# cpuboard_pic32mx_rev01.net
KiCad netlist of a schematic drawn in EAGLE
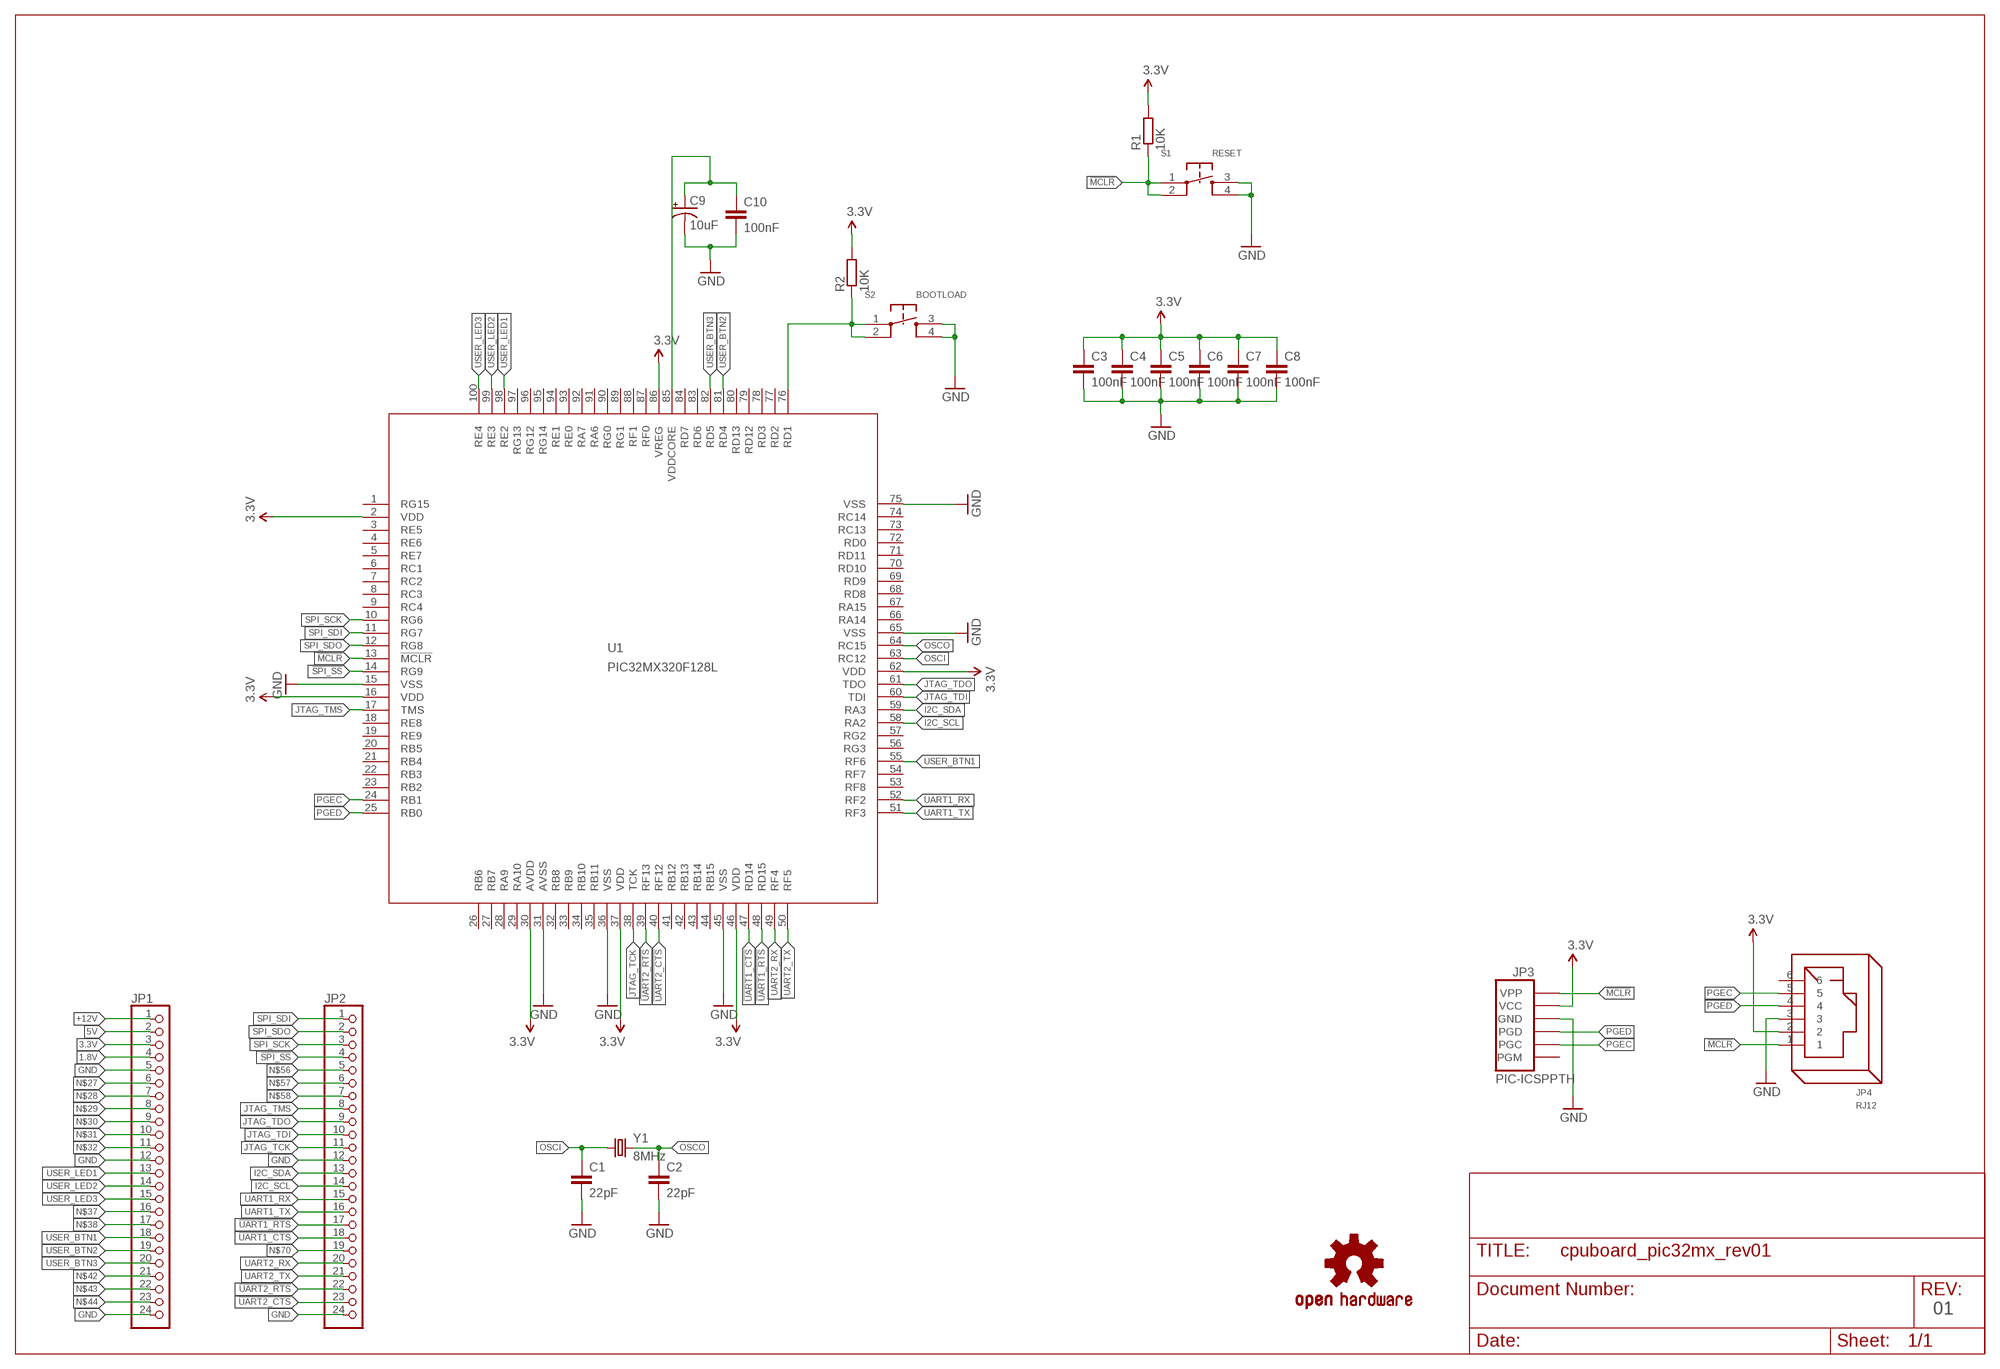
[diagram p0: schematic, sheet 1]

(export (version "E")
  (design (tool "Eeschema 10.0.6"))
  (components
    (comp (ref "C1")
      (value "22pF")
      (footprint "eagle-import:C0805K")
      (libsource (lib "eagle-import") (part "C-EUC0805K"))
    )
    (comp (ref "C2")
      (value "22pF")
      (footprint "eagle-import:C0805K")
      (libsource (lib "eagle-import") (part "C-EUC0805K"))
    )
    (comp (ref "C3")
      (value "100nF")
      (footprint "eagle-import:C0805K")
      (libsource (lib "eagle-import") (part "C-EUC0805K"))
    )
    (comp (ref "C4")
      (value "100nF")
      (footprint "eagle-import:C0805K")
      (libsource (lib "eagle-import") (part "C-EUC0805K"))
    )
    (comp (ref "C5")
      (value "100nF")
      (footprint "eagle-import:C0805K")
      (libsource (lib "eagle-import") (part "C-EUC0805K"))
    )
    (comp (ref "C6")
      (value "100nF")
      (footprint "eagle-import:C0805K")
      (libsource (lib "eagle-import") (part "C-EUC0805K"))
    )
    (comp (ref "C7")
      (value "100nF")
      (footprint "eagle-import:C0805K")
      (libsource (lib "eagle-import") (part "C-EUC0805K"))
    )
    (comp (ref "C8")
      (value "100nF")
      (footprint "eagle-import:C0805K")
      (libsource (lib "eagle-import") (part "C-EUC0805K"))
    )
    (comp (ref "C9")
      (value "10uF")
      (footprint "eagle-import:PANASONIC_D")
      (libsource (lib "eagle-import") (part "CAP_POLD"))
    )
    (comp (ref "C10")
      (value "100nF")
      (footprint "eagle-import:C0805K")
      (libsource (lib "eagle-import") (part "C-EUC0805K"))
    )
    (comp (ref "JP1")
      (value "PINHD-1X24")
      (footprint "eagle-import:1X24")
      (libsource (lib "eagle-import") (part "PINHD-1X24"))
    )
    (comp (ref "JP2")
      (value "PINHD-1X24")
      (footprint "eagle-import:1X24")
      (libsource (lib "eagle-import") (part "PINHD-1X24"))
    )
    (comp (ref "JP3")
      (value "PIC-ICSPPTH")
      (footprint "eagle-import:MOLEX-1X6")
      (libsource (lib "eagle-import") (part "PIC-ICSPPTH"))
    )
    (comp (ref "JP4")
      (value "RJ12")
      (footprint "eagle-import:RJ12")
      (libsource (lib "eagle-import") (part "RJ12"))
    )
    (comp (ref "R1")
      (value "10K")
      (footprint "eagle-import:R0805")
      (libsource (lib "eagle-import") (part "R-EU_R0805"))
    )
    (comp (ref "R2")
      (value "10K")
      (footprint "eagle-import:R0805")
      (libsource (lib "eagle-import") (part "R-EU_R0805"))
    )
    (comp (ref "S1")
      (value "RESET")
      (footprint "eagle-import:SWITCH_TROUGHHOLE")
      (libsource (lib "eagle-import") (part "SWITCH_TH"))
    )
    (comp (ref "S2")
      (value "BOOTLOAD")
      (footprint "eagle-import:SWITCH_TROUGHHOLE")
      (libsource (lib "eagle-import") (part "SWITCH_TH"))
    )
    (comp (ref "U$1")
      (value "OSHW-LOGOS")
      (footprint "eagle-import:OSHW-LOGO-S")
      (libsource (lib "eagle-import") (part "OSHW-LOGOS"))
    )
    (comp (ref "U1")
      (value "PIC32MX320F128L")
      (footprint "eagle-import:SQFP-S-12X12-100")
      (fields (field (name "MPN") "PIC32MX320F128L-80I/PT"))
      (libsource (lib "eagle-import") (part "PIC32MX320F128L"))
    )
    (comp (ref "Y1")
      (value "8MHz")
      (footprint "eagle-import:HC49UP")
      (libsource (lib "eagle-import") (part "CRYSTALSMD"))
    )
  )
  (nets
    (net (code "1") (name "+12V") (class "Default")
      (node (ref "JP1") (pin "1") (pinfunction "1_1") (pintype "passive"))
    )
    (net (code "2") (name "/~{MCLR}") (class "Default")
      (node (ref "JP3") (pin "6") (pinfunction "VPP_6") (pintype "bidirectional"))
      (node (ref "JP4") (pin "1") (pinfunction "1_1") (pintype "bidirectional"))
      (node (ref "R1") (pin "1") (pinfunction "1_1") (pintype "passive"))
      (node (ref "S1") (pin "1") (pintype "bidirectional"))
      (node (ref "S1") (pin "2") (pintype "bidirectional"))
      (node (ref "U1") (pin "13") (pinfunction "~{MCLR}_13") (pintype "input"))
    )
    (net (code "3") (name "/~{SPI_SS}") (class "Default")
      (node (ref "JP2") (pin "4") (pinfunction "4_4") (pintype "passive"))
      (node (ref "U1") (pin "14") (pinfunction "RG9_14") (pintype "bidirectional"))
    )
    (net (code "4") (name "/~{UART1_CTS}") (class "Default")
      (node (ref "JP2") (pin "18") (pinfunction "18_18") (pintype "passive"))
      (node (ref "U1") (pin "47") (pinfunction "RD14_47") (pintype "bidirectional"))
    )
    (net (code "5") (name "/~{UART1_RTS}") (class "Default")
      (node (ref "JP2") (pin "17") (pinfunction "17_17") (pintype "passive"))
      (node (ref "U1") (pin "48") (pinfunction "RD15_48") (pintype "bidirectional"))
    )
    (net (code "6") (name "/~{UART2_CTS}") (class "Default")
      (node (ref "JP2") (pin "23") (pinfunction "23_23") (pintype "passive"))
      (node (ref "U1") (pin "40") (pinfunction "RF12_40") (pintype "bidirectional"))
    )
    (net (code "7") (name "/~{UART2_RTS}") (class "Default")
      (node (ref "JP2") (pin "22") (pinfunction "22_22") (pintype "passive"))
      (node (ref "U1") (pin "39") (pinfunction "RF13_39") (pintype "bidirectional"))
    )
    (net (code "8") (name "1.8V") (class "Default")
      (node (ref "JP1") (pin "4") (pinfunction "4_4") (pintype "passive"))
    )
    (net (code "9") (name "3.3V") (class "Default")
      (node (ref "C3") (pin "1") (pinfunction "1_1") (pintype "passive"))
      (node (ref "C4") (pin "1") (pinfunction "1_1") (pintype "passive"))
      (node (ref "C5") (pin "1") (pinfunction "1_1") (pintype "passive"))
      (node (ref "C6") (pin "1") (pinfunction "1_1") (pintype "passive"))
      (node (ref "C7") (pin "1") (pinfunction "1_1") (pintype "passive"))
      (node (ref "C8") (pin "1") (pinfunction "1_1") (pintype "passive"))
      (node (ref "JP1") (pin "3") (pinfunction "3_3") (pintype "passive"))
      (node (ref "JP3") (pin "5") (pinfunction "VCC_5") (pintype "bidirectional"))
      (node (ref "JP4") (pin "2") (pinfunction "2_2") (pintype "bidirectional"))
      (node (ref "R1") (pin "2") (pinfunction "2_2") (pintype "passive"))
      (node (ref "R2") (pin "2") (pinfunction "2_2") (pintype "passive"))
      (node (ref "U1") (pin "16") (pinfunction "VDD_16") (pintype "power_in"))
      (node (ref "U1") (pin "2") (pinfunction "VDD_2") (pintype "power_in"))
      (node (ref "U1") (pin "30") (pinfunction "AVDD_30") (pintype "power_in"))
      (node (ref "U1") (pin "37") (pinfunction "VDD_37") (pintype "power_in"))
      (node (ref "U1") (pin "46") (pinfunction "VDD_46") (pintype "power_in"))
      (node (ref "U1") (pin "62") (pinfunction "VDD_62") (pintype "power_in"))
      (node (ref "U1") (pin "86") (pinfunction "VREG_86") (pintype "passive"))
    )
    (net (code "10") (name "5V") (class "Default")
      (node (ref "JP1") (pin "2") (pinfunction "2_2") (pintype "passive"))
    )
    (net (code "11") (name "GND") (class "Default")
      (node (ref "C1") (pin "2") (pinfunction "2_2") (pintype "passive"))
      (node (ref "C10") (pin "2") (pinfunction "2_2") (pintype "passive"))
      (node (ref "C2") (pin "2") (pinfunction "2_2") (pintype "passive"))
      (node (ref "C3") (pin "2") (pinfunction "2_2") (pintype "passive"))
      (node (ref "C4") (pin "2") (pinfunction "2_2") (pintype "passive"))
      (node (ref "C5") (pin "2") (pinfunction "2_2") (pintype "passive"))
      (node (ref "C6") (pin "2") (pinfunction "2_2") (pintype "passive"))
      (node (ref "C7") (pin "2") (pinfunction "2_2") (pintype "passive"))
      (node (ref "C8") (pin "2") (pinfunction "2_2") (pintype "passive"))
      (node (ref "C9") (pin "-") (pinfunction "-_-") (pintype "passive"))
      (node (ref "JP1") (pin "12") (pinfunction "12_12") (pintype "passive"))
      (node (ref "JP1") (pin "24") (pinfunction "24_24") (pintype "passive"))
      (node (ref "JP1") (pin "5") (pinfunction "5_5") (pintype "passive"))
      (node (ref "JP2") (pin "12") (pinfunction "12_12") (pintype "passive"))
      (node (ref "JP2") (pin "24") (pinfunction "24_24") (pintype "passive"))
      (node (ref "JP3") (pin "4") (pinfunction "GND_4") (pintype "bidirectional"))
      (node (ref "JP4") (pin "3") (pinfunction "3_3") (pintype "bidirectional"))
      (node (ref "S1") (pin "3") (pintype "bidirectional"))
      (node (ref "S1") (pin "4") (pintype "bidirectional"))
      (node (ref "S2") (pin "3") (pintype "bidirectional"))
      (node (ref "S2") (pin "4") (pintype "bidirectional"))
      (node (ref "U1") (pin "15") (pinfunction "VSS_15") (pintype "power_in"))
      (node (ref "U1") (pin "31") (pinfunction "AVSS_31") (pintype "power_in"))
      (node (ref "U1") (pin "36") (pinfunction "VSS_36") (pintype "power_in"))
      (node (ref "U1") (pin "45") (pinfunction "VSS_45") (pintype "power_in"))
      (node (ref "U1") (pin "65") (pinfunction "VSS_65") (pintype "power_in"))
      (node (ref "U1") (pin "75") (pinfunction "VSS_75") (pintype "power_in"))
    )
    (net (code "12") (name "I2C_SCL") (class "Default")
      (node (ref "JP2") (pin "14") (pinfunction "14_14") (pintype "passive"))
      (node (ref "U1") (pin "58") (pinfunction "RA2_58") (pintype "bidirectional"))
    )
    (net (code "13") (name "I2C_SDA") (class "Default")
      (node (ref "JP2") (pin "13") (pinfunction "13_13") (pintype "passive"))
      (node (ref "U1") (pin "59") (pinfunction "RA3_59") (pintype "bidirectional"))
    )
    (net (code "14") (name "JTAG_TCK") (class "Default")
      (node (ref "JP2") (pin "11") (pinfunction "11_11") (pintype "passive"))
      (node (ref "U1") (pin "38") (pinfunction "TCK_38") (pintype "input"))
    )
    (net (code "15") (name "JTAG_TDI") (class "Default")
      (node (ref "JP2") (pin "10") (pinfunction "10_10") (pintype "passive"))
      (node (ref "U1") (pin "60") (pinfunction "TDI_60") (pintype "input"))
    )
    (net (code "16") (name "JTAG_TDO") (class "Default")
      (node (ref "JP2") (pin "9") (pinfunction "9_9") (pintype "passive"))
      (node (ref "U1") (pin "61") (pinfunction "TDO_61") (pintype "output"))
    )
    (net (code "17") (name "JTAG_TMS") (class "Default")
      (node (ref "JP2") (pin "8") (pinfunction "8_8") (pintype "passive"))
      (node (ref "U1") (pin "17") (pinfunction "TMS_17") (pintype "input"))
    )
    (net (code "18") (name "N$27") (class "Default")
      (node (ref "JP1") (pin "6") (pinfunction "6_6") (pintype "passive"))
    )
    (net (code "19") (name "N$28") (class "Default")
      (node (ref "JP1") (pin "7") (pinfunction "7_7") (pintype "passive"))
    )
    (net (code "20") (name "N$29") (class "Default")
      (node (ref "JP1") (pin "8") (pinfunction "8_8") (pintype "passive"))
    )
    (net (code "21") (name "N$30") (class "Default")
      (node (ref "JP1") (pin "9") (pinfunction "9_9") (pintype "passive"))
    )
    (net (code "22") (name "N$31") (class "Default")
      (node (ref "JP1") (pin "10") (pinfunction "10_10") (pintype "passive"))
    )
    (net (code "23") (name "N$32") (class "Default")
      (node (ref "JP1") (pin "11") (pinfunction "11_11") (pintype "passive"))
    )
    (net (code "24") (name "N$37") (class "Default")
      (node (ref "JP1") (pin "16") (pinfunction "16_16") (pintype "passive"))
    )
    (net (code "25") (name "N$38") (class "Default")
      (node (ref "JP1") (pin "17") (pinfunction "17_17") (pintype "passive"))
    )
    (net (code "26") (name "N$42") (class "Default")
      (node (ref "JP1") (pin "21") (pinfunction "21_21") (pintype "passive"))
    )
    (net (code "27") (name "N$43") (class "Default")
      (node (ref "JP1") (pin "22") (pinfunction "22_22") (pintype "passive"))
    )
    (net (code "28") (name "N$44") (class "Default")
      (node (ref "JP1") (pin "23") (pinfunction "23_23") (pintype "passive"))
    )
    (net (code "29") (name "N$56") (class "Default")
      (node (ref "JP2") (pin "5") (pinfunction "5_5") (pintype "passive"))
    )
    (net (code "30") (name "N$57") (class "Default")
      (node (ref "JP2") (pin "6") (pinfunction "6_6") (pintype "passive"))
    )
    (net (code "31") (name "N$58") (class "Default")
      (node (ref "JP2") (pin "7") (pinfunction "7_7") (pintype "passive"))
    )
    (net (code "32") (name "N$70") (class "Default")
      (node (ref "JP2") (pin "19") (pinfunction "19_19") (pintype "passive"))
    )
    (net (code "33") (name "Net-(U1-RD1)") (class "Default")
      (node (ref "R2") (pin "1") (pinfunction "1_1") (pintype "passive"))
      (node (ref "S2") (pin "1") (pintype "bidirectional"))
      (node (ref "S2") (pin "2") (pintype "bidirectional"))
      (node (ref "U1") (pin "76") (pinfunction "RD1_76") (pintype "bidirectional"))
    )
    (net (code "34") (name "Net-(U1-VDDCORE)") (class "Default")
      (node (ref "C10") (pin "1") (pinfunction "1_1") (pintype "passive"))
      (node (ref "C9") (pin "+") (pinfunction "+_+") (pintype "passive"))
      (node (ref "U1") (pin "85") (pinfunction "VDDCORE_85") (pintype "power_in"))
    )
    (net (code "35") (name "OSCI") (class "Default")
      (node (ref "C1") (pin "1") (pinfunction "1_1") (pintype "passive"))
      (node (ref "U1") (pin "63") (pinfunction "RC12_63") (pintype "bidirectional"))
      (node (ref "Y1") (pin "1") (pinfunction "1_1") (pintype "passive"))
    )
    (net (code "36") (name "OSCO") (class "Default")
      (node (ref "C2") (pin "1") (pinfunction "1_1") (pintype "passive"))
      (node (ref "U1") (pin "64") (pinfunction "RC15_64") (pintype "bidirectional"))
      (node (ref "Y1") (pin "2") (pinfunction "2_2") (pintype "passive"))
    )
    (net (code "37") (name "PGEC") (class "Default")
      (node (ref "JP3") (pin "2") (pinfunction "PGC_2") (pintype "bidirectional"))
      (node (ref "JP4") (pin "5") (pinfunction "5_5") (pintype "bidirectional"))
      (node (ref "U1") (pin "24") (pinfunction "RB1_24") (pintype "bidirectional"))
    )
    (net (code "38") (name "PGED") (class "Default")
      (node (ref "JP3") (pin "3") (pinfunction "PGD_3") (pintype "bidirectional"))
      (node (ref "JP4") (pin "4") (pinfunction "4_4") (pintype "bidirectional"))
      (node (ref "U1") (pin "25") (pinfunction "RB0_25") (pintype "bidirectional"))
    )
    (net (code "39") (name "SPI_SCK") (class "Default")
      (node (ref "JP2") (pin "3") (pinfunction "3_3") (pintype "passive"))
      (node (ref "U1") (pin "10") (pinfunction "RG6_10") (pintype "bidirectional"))
    )
    (net (code "40") (name "SPI_SDI") (class "Default")
      (node (ref "JP2") (pin "1") (pinfunction "1_1") (pintype "passive"))
      (node (ref "U1") (pin "11") (pinfunction "RG7_11") (pintype "bidirectional"))
    )
    (net (code "41") (name "SPI_SDO") (class "Default")
      (node (ref "JP2") (pin "2") (pinfunction "2_2") (pintype "passive"))
      (node (ref "U1") (pin "12") (pinfunction "RG8_12") (pintype "bidirectional"))
    )
    (net (code "42") (name "UART1_RX") (class "Default")
      (node (ref "JP2") (pin "15") (pinfunction "15_15") (pintype "passive"))
      (node (ref "U1") (pin "52") (pinfunction "RF2_52") (pintype "bidirectional"))
    )
    (net (code "43") (name "UART1_TX") (class "Default")
      (node (ref "JP2") (pin "16") (pinfunction "16_16") (pintype "passive"))
      (node (ref "U1") (pin "51") (pinfunction "RF3_51") (pintype "bidirectional"))
    )
    (net (code "44") (name "UART2_RX") (class "Default")
      (node (ref "JP2") (pin "20") (pinfunction "20_20") (pintype "passive"))
      (node (ref "U1") (pin "49") (pinfunction "RF4_49") (pintype "bidirectional"))
    )
    (net (code "45") (name "UART2_TX") (class "Default")
      (node (ref "JP2") (pin "21") (pinfunction "21_21") (pintype "passive"))
      (node (ref "U1") (pin "50") (pinfunction "RF5_50") (pintype "bidirectional"))
    )
    (net (code "46") (name "USER_BTN1") (class "Default")
      (node (ref "JP1") (pin "18") (pinfunction "18_18") (pintype "passive"))
      (node (ref "U1") (pin "55") (pinfunction "RF6_55") (pintype "bidirectional"))
    )
    (net (code "47") (name "USER_BTN2") (class "Default")
      (node (ref "JP1") (pin "19") (pinfunction "19_19") (pintype "passive"))
      (node (ref "U1") (pin "81") (pinfunction "RD4_81") (pintype "bidirectional"))
    )
    (net (code "48") (name "USER_BTN3") (class "Default")
      (node (ref "JP1") (pin "20") (pinfunction "20_20") (pintype "passive"))
      (node (ref "U1") (pin "82") (pinfunction "RD5_82") (pintype "bidirectional"))
    )
    (net (code "49") (name "USER_LED1") (class "Default")
      (node (ref "JP1") (pin "13") (pinfunction "13_13") (pintype "passive"))
      (node (ref "U1") (pin "98") (pinfunction "RE2_98") (pintype "bidirectional"))
    )
    (net (code "50") (name "USER_LED2") (class "Default")
      (node (ref "JP1") (pin "14") (pinfunction "14_14") (pintype "passive"))
      (node (ref "U1") (pin "99") (pinfunction "RE3_99") (pintype "bidirectional"))
    )
    (net (code "51") (name "USER_LED3") (class "Default")
      (node (ref "JP1") (pin "15") (pinfunction "15_15") (pintype "passive"))
      (node (ref "U1") (pin "100") (pinfunction "RE4_100") (pintype "bidirectional"))
    )
    (net (code "52") (name "unconnected-(JP3-PGM-Pad1)") (class "Default")
      (node (ref "JP3") (pin "1") (pinfunction "PGM_1") (pintype "bidirectional"))
    )
    (net (code "53") (name "unconnected-(JP4-Pad6)") (class "Default")
      (node (ref "JP4") (pin "6") (pinfunction "6_6") (pintype "bidirectional"))
    )
    (net (code "54") (name "unconnected-(U1-RA6-Pad91)") (class "Default")
      (node (ref "U1") (pin "91") (pinfunction "RA6_91") (pintype "bidirectional"))
    )
    (net (code "55") (name "unconnected-(U1-RA7-Pad92)") (class "Default")
      (node (ref "U1") (pin "92") (pinfunction "RA7_92") (pintype "bidirectional"))
    )
    (net (code "56") (name "unconnected-(U1-RA9-Pad28)") (class "Default")
      (node (ref "U1") (pin "28") (pinfunction "RA9_28") (pintype "bidirectional"))
    )
    (net (code "57") (name "unconnected-(U1-RA10-Pad29)") (class "Default")
      (node (ref "U1") (pin "29") (pinfunction "RA10_29") (pintype "bidirectional"))
    )
    (net (code "58") (name "unconnected-(U1-RA14-Pad66)") (class "Default")
      (node (ref "U1") (pin "66") (pinfunction "RA14_66") (pintype "bidirectional"))
    )
    (net (code "59") (name "unconnected-(U1-RA15-Pad67)") (class "Default")
      (node (ref "U1") (pin "67") (pinfunction "RA15_67") (pintype "bidirectional"))
    )
    (net (code "60") (name "unconnected-(U1-RB2-Pad23)") (class "Default")
      (node (ref "U1") (pin "23") (pinfunction "RB2_23") (pintype "bidirectional"))
    )
    (net (code "61") (name "unconnected-(U1-RB3-Pad22)") (class "Default")
      (node (ref "U1") (pin "22") (pinfunction "RB3_22") (pintype "bidirectional"))
    )
    (net (code "62") (name "unconnected-(U1-RB4-Pad21)") (class "Default")
      (node (ref "U1") (pin "21") (pinfunction "RB4_21") (pintype "bidirectional"))
    )
    (net (code "63") (name "unconnected-(U1-RB5-Pad20)") (class "Default")
      (node (ref "U1") (pin "20") (pinfunction "RB5_20") (pintype "bidirectional"))
    )
    (net (code "64") (name "unconnected-(U1-RB6-Pad26)") (class "Default")
      (node (ref "U1") (pin "26") (pinfunction "RB6_26") (pintype "bidirectional"))
    )
    (net (code "65") (name "unconnected-(U1-RB7-Pad27)") (class "Default")
      (node (ref "U1") (pin "27") (pinfunction "RB7_27") (pintype "bidirectional"))
    )
    (net (code "66") (name "unconnected-(U1-RB8-Pad32)") (class "Default")
      (node (ref "U1") (pin "32") (pinfunction "RB8_32") (pintype "bidirectional"))
    )
    (net (code "67") (name "unconnected-(U1-RB9-Pad33)") (class "Default")
      (node (ref "U1") (pin "33") (pinfunction "RB9_33") (pintype "bidirectional"))
    )
    (net (code "68") (name "unconnected-(U1-RB10-Pad34)") (class "Default")
      (node (ref "U1") (pin "34") (pinfunction "RB10_34") (pintype "bidirectional"))
    )
    (net (code "69") (name "unconnected-(U1-RB11-Pad35)") (class "Default")
      (node (ref "U1") (pin "35") (pinfunction "RB11_35") (pintype "bidirectional"))
    )
    (net (code "70") (name "unconnected-(U1-RB12-Pad41)") (class "Default")
      (node (ref "U1") (pin "41") (pinfunction "RB12_41") (pintype "bidirectional"))
    )
    (net (code "71") (name "unconnected-(U1-RB13-Pad42)") (class "Default")
      (node (ref "U1") (pin "42") (pinfunction "RB13_42") (pintype "bidirectional"))
    )
    (net (code "72") (name "unconnected-(U1-RB14-Pad43)") (class "Default")
      (node (ref "U1") (pin "43") (pinfunction "RB14_43") (pintype "bidirectional"))
    )
    (net (code "73") (name "unconnected-(U1-RB15-Pad44)") (class "Default")
      (node (ref "U1") (pin "44") (pinfunction "RB15_44") (pintype "bidirectional"))
    )
    (net (code "74") (name "unconnected-(U1-RC1-Pad6)") (class "Default")
      (node (ref "U1") (pin "6") (pinfunction "RC1_6") (pintype "bidirectional"))
    )
    (net (code "75") (name "unconnected-(U1-RC2-Pad7)") (class "Default")
      (node (ref "U1") (pin "7") (pinfunction "RC2_7") (pintype "bidirectional"))
    )
    (net (code "76") (name "unconnected-(U1-RC3-Pad8)") (class "Default")
      (node (ref "U1") (pin "8") (pinfunction "RC3_8") (pintype "bidirectional"))
    )
    (net (code "77") (name "unconnected-(U1-RC4-Pad9)") (class "Default")
      (node (ref "U1") (pin "9") (pinfunction "RC4_9") (pintype "bidirectional"))
    )
    (net (code "78") (name "unconnected-(U1-RC13-Pad73)") (class "Default")
      (node (ref "U1") (pin "73") (pinfunction "RC13_73") (pintype "bidirectional"))
    )
    (net (code "79") (name "unconnected-(U1-RC14-Pad74)") (class "Default")
      (node (ref "U1") (pin "74") (pinfunction "RC14_74") (pintype "bidirectional"))
    )
    (net (code "80") (name "unconnected-(U1-RD0-Pad72)") (class "Default")
      (node (ref "U1") (pin "72") (pinfunction "RD0_72") (pintype "bidirectional"))
    )
    (net (code "81") (name "unconnected-(U1-RD2-Pad77)") (class "Default")
      (node (ref "U1") (pin "77") (pinfunction "RD2_77") (pintype "bidirectional"))
    )
    (net (code "82") (name "unconnected-(U1-RD3-Pad78)") (class "Default")
      (node (ref "U1") (pin "78") (pinfunction "RD3_78") (pintype "bidirectional"))
    )
    (net (code "83") (name "unconnected-(U1-RD6-Pad83)") (class "Default")
      (node (ref "U1") (pin "83") (pinfunction "RD6_83") (pintype "bidirectional"))
    )
    (net (code "84") (name "unconnected-(U1-RD7-Pad84)") (class "Default")
      (node (ref "U1") (pin "84") (pinfunction "RD7_84") (pintype "bidirectional"))
    )
    (net (code "85") (name "unconnected-(U1-RD8-Pad68)") (class "Default")
      (node (ref "U1") (pin "68") (pinfunction "RD8_68") (pintype "bidirectional"))
    )
    (net (code "86") (name "unconnected-(U1-RD9-Pad69)") (class "Default")
      (node (ref "U1") (pin "69") (pinfunction "RD9_69") (pintype "bidirectional"))
    )
    (net (code "87") (name "unconnected-(U1-RD10-Pad70)") (class "Default")
      (node (ref "U1") (pin "70") (pinfunction "RD10_70") (pintype "bidirectional"))
    )
    (net (code "88") (name "unconnected-(U1-RD11-Pad71)") (class "Default")
      (node (ref "U1") (pin "71") (pinfunction "RD11_71") (pintype "bidirectional"))
    )
    (net (code "89") (name "unconnected-(U1-RD12-Pad79)") (class "Default")
      (node (ref "U1") (pin "79") (pinfunction "RD12_79") (pintype "bidirectional"))
    )
    (net (code "90") (name "unconnected-(U1-RD13-Pad80)") (class "Default")
      (node (ref "U1") (pin "80") (pinfunction "RD13_80") (pintype "bidirectional"))
    )
    (net (code "91") (name "unconnected-(U1-RE0-Pad93)") (class "Default")
      (node (ref "U1") (pin "93") (pinfunction "RE0_93") (pintype "bidirectional"))
    )
    (net (code "92") (name "unconnected-(U1-RE1-Pad94)") (class "Default")
      (node (ref "U1") (pin "94") (pinfunction "RE1_94") (pintype "bidirectional"))
    )
    (net (code "93") (name "unconnected-(U1-RE5-Pad3)") (class "Default")
      (node (ref "U1") (pin "3") (pinfunction "RE5_3") (pintype "bidirectional"))
    )
    (net (code "94") (name "unconnected-(U1-RE6-Pad4)") (class "Default")
      (node (ref "U1") (pin "4") (pinfunction "RE6_4") (pintype "bidirectional"))
    )
    (net (code "95") (name "unconnected-(U1-RE7-Pad5)") (class "Default")
      (node (ref "U1") (pin "5") (pinfunction "RE7_5") (pintype "bidirectional"))
    )
    (net (code "96") (name "unconnected-(U1-RE8-Pad18)") (class "Default")
      (node (ref "U1") (pin "18") (pinfunction "RE8_18") (pintype "bidirectional"))
    )
    (net (code "97") (name "unconnected-(U1-RE9-Pad19)") (class "Default")
      (node (ref "U1") (pin "19") (pinfunction "RE9_19") (pintype "bidirectional"))
    )
    (net (code "98") (name "unconnected-(U1-RF0-Pad87)") (class "Default")
      (node (ref "U1") (pin "87") (pinfunction "RF0_87") (pintype "bidirectional"))
    )
    (net (code "99") (name "unconnected-(U1-RF1-Pad88)") (class "Default")
      (node (ref "U1") (pin "88") (pinfunction "RF1_88") (pintype "bidirectional"))
    )
    (net (code "100") (name "unconnected-(U1-RF7-Pad54)") (class "Default")
      (node (ref "U1") (pin "54") (pinfunction "RF7_54") (pintype "bidirectional"))
    )
    (net (code "101") (name "unconnected-(U1-RF8-Pad53)") (class "Default")
      (node (ref "U1") (pin "53") (pinfunction "RF8_53") (pintype "bidirectional"))
    )
    (net (code "102") (name "unconnected-(U1-RG0-Pad90)") (class "Default")
      (node (ref "U1") (pin "90") (pinfunction "RG0_90") (pintype "bidirectional"))
    )
    (net (code "103") (name "unconnected-(U1-RG1-Pad89)") (class "Default")
      (node (ref "U1") (pin "89") (pinfunction "RG1_89") (pintype "bidirectional"))
    )
    (net (code "104") (name "unconnected-(U1-RG2-Pad57)") (class "Default")
      (node (ref "U1") (pin "57") (pinfunction "RG2_57") (pintype "bidirectional"))
    )
    (net (code "105") (name "unconnected-(U1-RG3-Pad56)") (class "Default")
      (node (ref "U1") (pin "56") (pinfunction "RG3_56") (pintype "bidirectional"))
    )
    (net (code "106") (name "unconnected-(U1-RG12-Pad96)") (class "Default")
      (node (ref "U1") (pin "96") (pinfunction "RG12_96") (pintype "bidirectional"))
    )
    (net (code "107") (name "unconnected-(U1-RG13-Pad97)") (class "Default")
      (node (ref "U1") (pin "97") (pinfunction "RG13_97") (pintype "bidirectional"))
    )
    (net (code "108") (name "unconnected-(U1-RG14-Pad95)") (class "Default")
      (node (ref "U1") (pin "95") (pinfunction "RG14_95") (pintype "bidirectional"))
    )
    (net (code "109") (name "unconnected-(U1-RG15-Pad1)") (class "Default")
      (node (ref "U1") (pin "1") (pinfunction "RG15_1") (pintype "bidirectional"))
    )
  )
)
